# T02_noclock_rev3.net
KiCad netlist of a schematic drawn in EAGLE
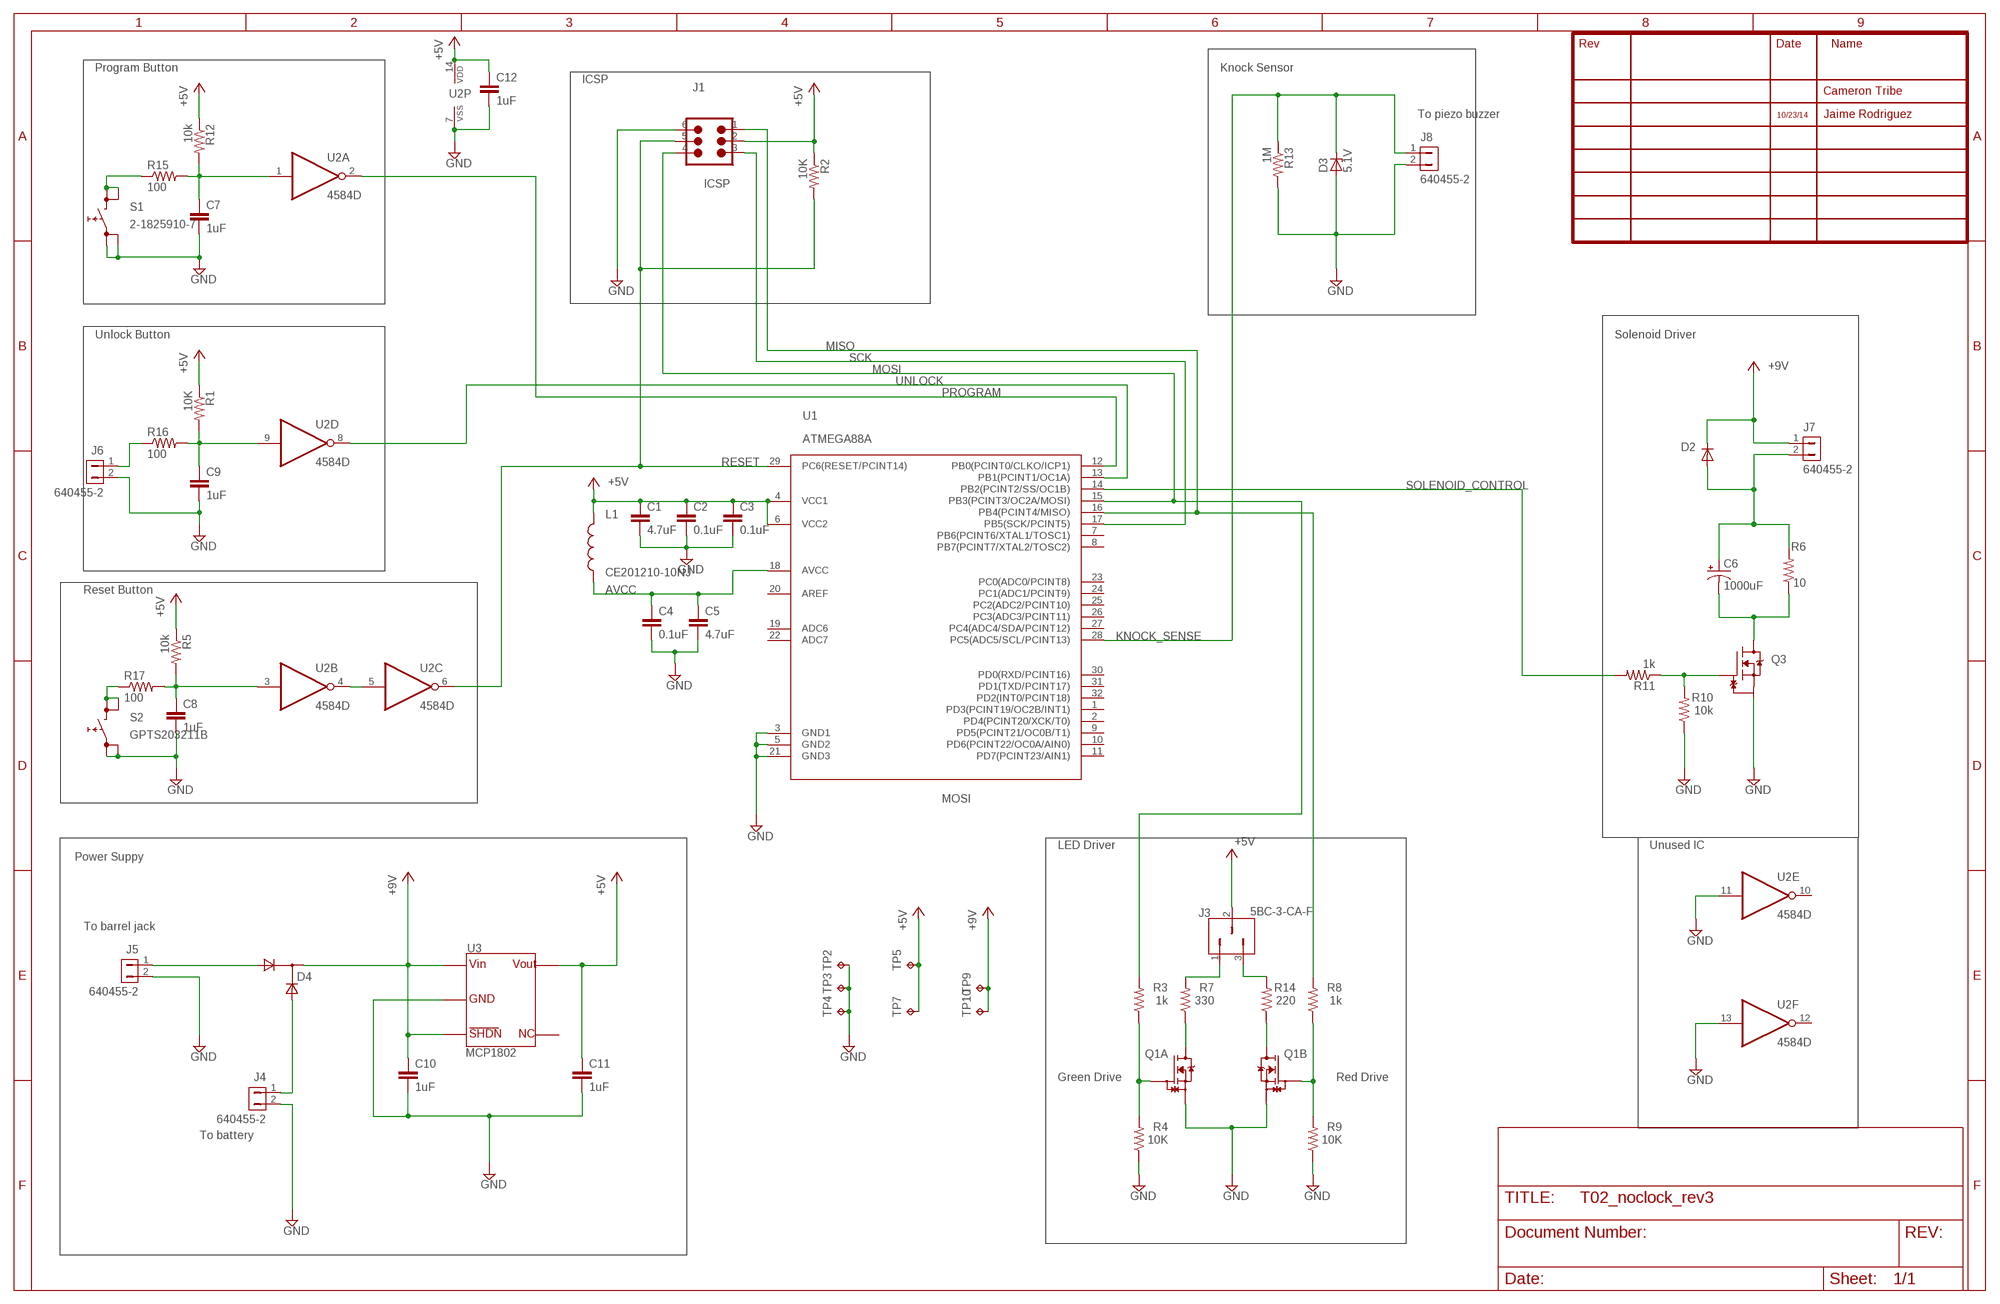
[diagram p0: schematic, sheet 1]

(export (version "E")
  (design (tool "Eeschema 10.0.6"))
  (components
    (comp (ref "C1")
      (value "4.7uF")
      (footprint "eagle-import:C0805")
      (fields (field (name "PARTNUM") "CL21A475KOFNNNE"))
      (libsource (lib "eagle-import") (part "C-EUC0805"))
    )
    (comp (ref "C2")
      (value "0.1uF")
      (footprint "eagle-import:C0805")
      (fields (field (name "PARTNUM") "GRM155R61A104KA01D"))
      (libsource (lib "eagle-import") (part "C-EUC0805"))
    )
    (comp (ref "C3")
      (value "0.1uF")
      (footprint "eagle-import:C0805")
      (fields (field (name "PARTNUM") "GRM155R61A104KA01D"))
      (libsource (lib "eagle-import") (part "C-EUC0805"))
    )
    (comp (ref "C4")
      (value "0.1uF")
      (footprint "eagle-import:C0805")
      (fields (field (name "PARTNUM") "GRM155R61A104KA01D"))
      (libsource (lib "eagle-import") (part "C-EUC0805"))
    )
    (comp (ref "C5")
      (value "4.7uF")
      (footprint "eagle-import:C0805")
      (fields (field (name "PARTNUM") "CL21A475KOFNNNE"))
      (libsource (lib "eagle-import") (part "C-EUC0805"))
    )
    (comp (ref "C6")
      (value "1000uF")
      (footprint "eagle-import:EKY-100ELL102MH20D")
      (libsource (lib "eagle-import") (part "EKY-100ELL102MH20D"))
    )
    (comp (ref "C7")
      (value "1uF")
      (footprint "eagle-import:C0805")
      (fields (field (name "PARTNUM") "CL21B105KBFNNNE"))
      (libsource (lib "eagle-import") (part "C-EUC0805"))
    )
    (comp (ref "C8")
      (value "1uF")
      (footprint "eagle-import:C0805")
      (fields (field (name "PARTNUM") "CL21B105KBFNNNE"))
      (libsource (lib "eagle-import") (part "C-EUC0805"))
    )
    (comp (ref "C9")
      (value "1uF")
      (footprint "eagle-import:C0805")
      (fields (field (name "PARTNUM") "CL21B105KBFNNNE"))
      (libsource (lib "eagle-import") (part "C-EUC0805"))
    )
    (comp (ref "C10")
      (value "1uF")
      (footprint "eagle-import:C0805")
      (fields (field (name "PARTNUM") "CL21B105KBFNNNE"))
      (libsource (lib "eagle-import") (part "C-EUC0805"))
    )
    (comp (ref "C11")
      (value "1uF")
      (footprint "eagle-import:C0805")
      (fields (field (name "PARTNUM") "CL21B105KBFNNNE"))
      (libsource (lib "eagle-import") (part "C-EUC0805"))
    )
    (comp (ref "C12")
      (value "1uF")
      (footprint "eagle-import:C0805")
      (fields (field (name "PARTNUM") "CL21B105KBFNNNE"))
      (libsource (lib "eagle-import") (part "C-EUC0805"))
    )
    (comp (ref "D2")
      (value "GF1")
      (footprint "eagle-import:SMA-DO214AC")
      (fields (field (name "PARTNUM") "S1J"))
      (libsource (lib "eagle-import") (part "GF1"))
    )
    (comp (ref "D3")
      (value "5.1V")
      (footprint "eagle-import:SOT23")
      (fields (field (name "PARTNUM") "BZX84C4V7-TP "))
      (libsource (lib "eagle-import") (part "ZENER-DIODESOT23"))
    )
    (comp (ref "D4")
      (value "PMEG2005CT,215")
      (footprint "eagle-import:SOT-23")
      (libsource (lib "eagle-import") (part "PMEG2005CT,215"))
    )
    (comp (ref "J1")
      (value "ICSP")
      (footprint "eagle-import:ICSP")
      (libsource (lib "eagle-import") (part "ICSP"))
    )
    (comp (ref "J3")
      (value "5BC-3-CA-F")
      (footprint "eagle-import:3_PIN_CONNECTOR")
      (libsource (lib "eagle-import") (part "5BC-3-CA-F"))
    )
    (comp (ref "J4")
      (value "640455-2")
      (footprint "eagle-import:2-PIN_CONNECTOR")
      (libsource (lib "eagle-import") (part "640455-2"))
    )
    (comp (ref "J5")
      (value "640455-2")
      (footprint "eagle-import:2-PIN_CONNECTOR")
      (libsource (lib "eagle-import") (part "640455-2"))
    )
    (comp (ref "J6")
      (value "640455-2")
      (footprint "eagle-import:2-PIN_CONNECTOR")
      (libsource (lib "eagle-import") (part "640455-2"))
    )
    (comp (ref "J7")
      (value "640455-2")
      (footprint "eagle-import:2-PIN_CONNECTOR")
      (libsource (lib "eagle-import") (part "640455-2"))
    )
    (comp (ref "J8")
      (value "640455-2")
      (footprint "eagle-import:2-PIN_CONNECTOR")
      (libsource (lib "eagle-import") (part "640455-2"))
    )
    (comp (ref "L1")
      (value "CE201210-10NJ")
      (footprint "eagle-import:R0805")
      (libsource (lib "eagle-import") (part "CE201210-10NJ"))
    )
    (comp (ref "Q1")
      (value "DMN63D8LDW-7")
      (footprint "eagle-import:SOT363")
      (fields (field (name "PARTNUM") "DMN63D8LDW-7"))
      (libsource (lib "eagle-import") (part "DMN63D8LDW-7"))
    )
    (comp (ref "Q3")
      (value "DMG1012UW-7")
      (footprint "eagle-import:SOT323")
      (libsource (lib "eagle-import") (part "DMG1012UW-7"))
    )
    (comp (ref "R1")
      (value "10K")
      (footprint "eagle-import:R0805")
      (fields (field (name "PARTNUM") "ESR10EZPJ103"))
      (libsource (lib "eagle-import") (part "R-US_R0805"))
    )
    (comp (ref "R2")
      (value "10K")
      (footprint "eagle-import:R0805")
      (fields (field (name "PARTNUM") "ESR10EZPJ103"))
      (libsource (lib "eagle-import") (part "R-US_R0805"))
    )
    (comp (ref "R3")
      (value "1k")
      (footprint "eagle-import:R0805")
      (fields (field (name "PARTNUM") "MCR10ERTF1001"))
      (libsource (lib "eagle-import") (part "R-US_R0805"))
    )
    (comp (ref "R4")
      (value "10K")
      (footprint "eagle-import:R0805")
      (fields (field (name "PARTNUM") "ESR10EZPJ103"))
      (libsource (lib "eagle-import") (part "R-US_R0805"))
    )
    (comp (ref "R5")
      (value "10k")
      (footprint "eagle-import:R0805")
      (fields (field (name "PARTNUM") "ESR10EZPJ103"))
      (libsource (lib "eagle-import") (part "R-US_R0805"))
    )
    (comp (ref "R6")
      (value "10")
      (footprint "eagle-import:R2512")
      (fields (field (name "PARTNUM") "CRM2512-JW-100ELF "))
      (libsource (lib "eagle-import") (part "R-US_R2512"))
    )
    (comp (ref "R7")
      (value "330")
      (footprint "eagle-import:R0805")
      (fields (field (name "PARTNUM") "MCR10ERTF3300"))
      (libsource (lib "eagle-import") (part "R-US_R0805"))
    )
    (comp (ref "R8")
      (value "1k")
      (footprint "eagle-import:R0805")
      (fields (field (name "PARTNUM") "MCR10ERTF1001"))
      (libsource (lib "eagle-import") (part "R-US_R0805"))
    )
    (comp (ref "R9")
      (value "10K")
      (footprint "eagle-import:R0805")
      (fields (field (name "PARTNUM") "ESR10EZPJ103"))
      (libsource (lib "eagle-import") (part "R-US_R0805"))
    )
    (comp (ref "R10")
      (value "10k")
      (footprint "eagle-import:R0805")
      (fields (field (name "PARTNUM") "ESR10EZPJ103"))
      (libsource (lib "eagle-import") (part "R-US_R0805"))
    )
    (comp (ref "R11")
      (value "1k")
      (footprint "eagle-import:R0805")
      (fields (field (name "PARTNUM") "MCR10ERTF1001"))
      (libsource (lib "eagle-import") (part "R-US_R0805"))
    )
    (comp (ref "R12")
      (value "10k")
      (footprint "eagle-import:R0805")
      (fields (field (name "PARTNUM") "ESR10EZPJ103"))
      (libsource (lib "eagle-import") (part "R-US_R0805"))
    )
    (comp (ref "R13")
      (value "1M")
      (footprint "eagle-import:R0805")
      (fields (field (name "PARTNUM") "RMCF0805JT1M00"))
      (libsource (lib "eagle-import") (part "R-US_R0805"))
    )
    (comp (ref "R14")
      (value "220")
      (footprint "eagle-import:R0805")
      (fields (field (name "PARTNUM") "RMCF0805FT220R"))
      (libsource (lib "eagle-import") (part "R-US_R0805"))
    )
    (comp (ref "R15")
      (value "100")
      (footprint "eagle-import:R0805")
      (fields (field (name "PARTNUM") "ESR10EZPJ103"))
      (libsource (lib "eagle-import") (part "R-US_R0805"))
    )
    (comp (ref "R16")
      (value "100")
      (footprint "eagle-import:R0805")
      (fields (field (name "PARTNUM") "ESR10EZPJ103"))
      (libsource (lib "eagle-import") (part "R-US_R0805"))
    )
    (comp (ref "R17")
      (value "100")
      (footprint "eagle-import:R0805")
      (fields (field (name "PARTNUM") "ESR10EZPJ103"))
      (libsource (lib "eagle-import") (part "R-US_R0805"))
    )
    (comp (ref "S1")
      (value "2-1825910-7")
      (footprint "eagle-import:FSM14JH")
      (libsource (lib "eagle-import") (part "2-1825910-7"))
    )
    (comp (ref "S2")
      (value "GPTS203211B")
      (footprint "eagle-import:GPTS203211B")
      (libsource (lib "eagle-import") (part "GPTS203211B"))
    )
    (comp (ref "TP2")
      (value "TPTP19R")
      (footprint "eagle-import:TP19R")
      (libsource (lib "eagle-import") (part "TPTP19R"))
    )
    (comp (ref "TP3")
      (value "TPTP19R")
      (footprint "eagle-import:TP19R")
      (libsource (lib "eagle-import") (part "TPTP19R"))
    )
    (comp (ref "TP4")
      (value "TPTP19R")
      (footprint "eagle-import:TP19R")
      (libsource (lib "eagle-import") (part "TPTP19R"))
    )
    (comp (ref "TP5")
      (value "TPTP19R")
      (footprint "eagle-import:TP19R")
      (libsource (lib "eagle-import") (part "TPTP19R"))
    )
    (comp (ref "TP7")
      (value "TPTP19R")
      (footprint "eagle-import:TP19R")
      (libsource (lib "eagle-import") (part "TPTP19R"))
    )
    (comp (ref "TP9")
      (value "TPTP19R")
      (footprint "eagle-import:TP19R")
      (libsource (lib "eagle-import") (part "TPTP19R"))
    )
    (comp (ref "TP10")
      (value "TPTP19R")
      (footprint "eagle-import:TP19R")
      (libsource (lib "eagle-import") (part "TPTP19R"))
    )
    (comp (ref "U1")
      (value "ATMEGA88A")
      (footprint "eagle-import:TQFP32")
      (libsource (lib "eagle-import") (part "ATMEGA88A"))
    )
    (comp (ref "U2")
      (value "4584D")
      (footprint "eagle-import:SO14")
      (fields (field (name "PARTNUM") "4584D"))
      (libsource (lib "eagle-import") (part "4584D"))
    )
    (comp (ref "U3")
      (value "MCP1802")
      (footprint "eagle-import:SOT23-5")
      (libsource (lib "eagle-import") (part "MCP1802"))
    )
  )
  (nets
    (net (code "1") (name "+5V") (class "Default")
      (node (ref "C1") (pin "1") (pinfunction "1_1") (pintype "passive"))
      (node (ref "C11") (pin "1") (pinfunction "1_1") (pintype "passive"))
      (node (ref "C12") (pin "1") (pinfunction "1_1") (pintype "passive"))
      (node (ref "C2") (pin "1") (pinfunction "1_1") (pintype "passive"))
      (node (ref "C3") (pin "1") (pinfunction "1_1") (pintype "passive"))
      (node (ref "J1") (pin "2") (pinfunction "2_2") (pintype "passive"))
      (node (ref "J3") (pin "2") (pinfunction "2_2") (pintype "passive"))
      (node (ref "L1") (pin "2") (pinfunction "2_2") (pintype "passive"))
      (node (ref "R1") (pin "1") (pinfunction "1_1") (pintype "passive"))
      (node (ref "R12") (pin "1") (pinfunction "1_1") (pintype "passive"))
      (node (ref "R2") (pin "1") (pinfunction "1_1") (pintype "passive"))
      (node (ref "R5") (pin "1") (pinfunction "1_1") (pintype "passive"))
      (node (ref "TP5") (pin "TP") (pinfunction "TP_TP") (pintype "input"))
      (node (ref "TP7") (pin "TP") (pinfunction "TP_TP") (pintype "input"))
      (node (ref "U1") (pin "4") (pinfunction "VCC1_4") (pintype "power_in"))
      (node (ref "U1") (pin "6") (pinfunction "VCC2_6") (pintype "passive"))
      (node (ref "U2") (pin "14") (pinfunction "VDD_14") (pintype "power_in"))
      (node (ref "U3") (pin "5") (pinfunction "VOUT_5") (pintype "passive"))
    )
    (net (code "2") (name "+9V") (class "Default")
      (node (ref "C10") (pin "1") (pinfunction "1_1") (pintype "passive"))
      (node (ref "D2") (pin "K") (pinfunction "C_K") (pintype "passive"))
      (node (ref "D4") (pin "2") (pinfunction "C_2") (pintype "passive"))
      (node (ref "J7") (pin "1") (pinfunction "1_1") (pintype "passive"))
      (node (ref "TP10") (pin "TP") (pinfunction "TP_TP") (pintype "input"))
      (node (ref "TP9") (pin "TP") (pinfunction "TP_TP") (pintype "input"))
      (node (ref "U3") (pin "1") (pinfunction "VIN_1") (pintype "passive"))
      (node (ref "U3") (pin "3") (pinfunction "SHDN_3") (pintype "passive"))
    )
    (net (code "3") (name "/AVCC") (class "Default")
      (node (ref "C4") (pin "1") (pinfunction "1_1") (pintype "passive"))
      (node (ref "C5") (pin "1") (pinfunction "1_1") (pintype "passive"))
      (node (ref "L1") (pin "1") (pinfunction "1_1") (pintype "passive"))
      (node (ref "U1") (pin "18") (pinfunction "AVCC_18") (pintype "power_in"))
    )
    (net (code "4") (name "/KNOCK_SENSE") (class "Default")
      (node (ref "D3") (pin "3") (pinfunction "C_3") (pintype "passive"))
      (node (ref "J8") (pin "1") (pinfunction "1_1") (pintype "passive"))
      (node (ref "R13") (pin "1") (pinfunction "1_1") (pintype "passive"))
      (node (ref "U1") (pin "28") (pinfunction "PC5(ADC5/SCL/PCINT13)_28") (pintype "bidirectional"))
    )
    (net (code "5") (name "/MISO") (class "Default")
      (node (ref "J1") (pin "1") (pinfunction "1_1") (pintype "passive"))
      (node (ref "R8") (pin "2") (pinfunction "2_2") (pintype "passive"))
      (node (ref "U1") (pin "16") (pinfunction "PB4(PCINT4/MISO)_16") (pintype "bidirectional"))
    )
    (net (code "6") (name "/MOSI") (class "Default")
      (node (ref "J1") (pin "4") (pinfunction "4_4") (pintype "passive"))
      (node (ref "R3") (pin "2") (pinfunction "2_2") (pintype "passive"))
      (node (ref "U1") (pin "15") (pinfunction "PB3(PCINT3/OC2A/MOSI)_15") (pintype "bidirectional"))
    )
    (net (code "7") (name "/PROGRAM") (class "Default")
      (node (ref "U1") (pin "12") (pinfunction "PB0(PCINT0/CLKO/ICP1)_12") (pintype "bidirectional"))
      (node (ref "U2") (pin "2") (pinfunction "O_2") (pintype "output"))
    )
    (net (code "8") (name "/RESET") (class "Default")
      (node (ref "J1") (pin "5") (pinfunction "5_5") (pintype "passive"))
      (node (ref "R2") (pin "2") (pinfunction "2_2") (pintype "passive"))
      (node (ref "U1") (pin "29") (pinfunction "PC6(RESET/PCINT14)_29") (pintype "bidirectional"))
      (node (ref "U2") (pin "6") (pinfunction "O_6") (pintype "output"))
    )
    (net (code "9") (name "/SCK") (class "Default")
      (node (ref "J1") (pin "3") (pinfunction "3_3") (pintype "passive"))
      (node (ref "U1") (pin "17") (pinfunction "PB5(SCK/PCINT5)_17") (pintype "bidirectional"))
    )
    (net (code "10") (name "/SOLENOID_CONTROL") (class "Default")
      (node (ref "R11") (pin "2") (pinfunction "2_2") (pintype "passive"))
      (node (ref "U1") (pin "14") (pinfunction "PB2(PCINT2/SS/OC1B)_14") (pintype "bidirectional"))
    )
    (net (code "11") (name "/UNLOCK") (class "Default")
      (node (ref "U1") (pin "13") (pinfunction "PB1(PCINT1/OC1A)_13") (pintype "bidirectional"))
      (node (ref "U2") (pin "8") (pinfunction "O_8") (pintype "output"))
    )
    (net (code "12") (name "GND") (class "Default")
      (node (ref "C1") (pin "2") (pinfunction "2_2") (pintype "passive"))
      (node (ref "C10") (pin "2") (pinfunction "2_2") (pintype "passive"))
      (node (ref "C11") (pin "2") (pinfunction "2_2") (pintype "passive"))
      (node (ref "C12") (pin "2") (pinfunction "2_2") (pintype "passive"))
      (node (ref "C2") (pin "2") (pinfunction "2_2") (pintype "passive"))
      (node (ref "C3") (pin "2") (pinfunction "2_2") (pintype "passive"))
      (node (ref "C4") (pin "2") (pinfunction "2_2") (pintype "passive"))
      (node (ref "C5") (pin "2") (pinfunction "2_2") (pintype "passive"))
      (node (ref "C7") (pin "2") (pinfunction "2_2") (pintype "passive"))
      (node (ref "C8") (pin "2") (pinfunction "2_2") (pintype "passive"))
      (node (ref "C9") (pin "2") (pinfunction "2_2") (pintype "passive"))
      (node (ref "D3") (pin "1") (pinfunction "A_1") (pintype "passive"))
      (node (ref "J1") (pin "6") (pinfunction "6_6") (pintype "passive"))
      (node (ref "J4") (pin "2") (pinfunction "2_2") (pintype "passive"))
      (node (ref "J5") (pin "2") (pinfunction "2_2") (pintype "passive"))
      (node (ref "J6") (pin "2") (pinfunction "2_2") (pintype "passive"))
      (node (ref "J8") (pin "2") (pinfunction "2_2") (pintype "passive"))
      (node (ref "Q1") (pin "S1") (pinfunction "S_S1") (pintype "passive"))
      (node (ref "Q1") (pin "S2") (pinfunction "S_S2") (pintype "passive"))
      (node (ref "Q3") (pin "3") (pinfunction "S_3") (pintype "passive"))
      (node (ref "R10") (pin "1") (pinfunction "1_1") (pintype "passive"))
      (node (ref "R13") (pin "2") (pinfunction "2_2") (pintype "passive"))
      (node (ref "R4") (pin "1") (pinfunction "1_1") (pintype "passive"))
      (node (ref "R9") (pin "1") (pinfunction "1_1") (pintype "passive"))
      (node (ref "S1") (pin "1") (pinfunction "1_1") (pintype "passive"))
      (node (ref "S1") (pin "2") (pinfunction "2_2") (pintype "passive"))
      (node (ref "S2") (pin "1") (pinfunction "1_1") (pintype "passive"))
      (node (ref "S2") (pin "2") (pinfunction "2_2") (pintype "passive"))
      (node (ref "TP2") (pin "TP") (pinfunction "TP_TP") (pintype "input"))
      (node (ref "TP3") (pin "TP") (pinfunction "TP_TP") (pintype "input"))
      (node (ref "TP4") (pin "TP") (pinfunction "TP_TP") (pintype "input"))
      (node (ref "U1") (pin "21") (pinfunction "GND3_21") (pintype "power_in"))
      (node (ref "U1") (pin "3") (pinfunction "GND1_3") (pintype "power_in"))
      (node (ref "U1") (pin "5") (pinfunction "GND2_5") (pintype "power_in"))
      (node (ref "U2") (pin "11") (pinfunction "I_11") (pintype "input"))
      (node (ref "U2") (pin "13") (pinfunction "I_13") (pintype "input"))
      (node (ref "U2") (pin "7") (pinfunction "VSS_7") (pintype "power_in"))
      (node (ref "U3") (pin "2") (pinfunction "GND_2") (pintype "power_in"))
    )
    (net (code "13") (name "Net-(C6-Pad+)") (class "Default")
      (node (ref "C6") (pin "+") (pinfunction "+_+") (pintype "passive"))
      (node (ref "D2") (pin "A") (pinfunction "A_A") (pintype "passive"))
      (node (ref "J7") (pin "2") (pinfunction "2_2") (pintype "passive"))
      (node (ref "R6") (pin "2") (pinfunction "2_2") (pintype "passive"))
    )
    (net (code "14") (name "Net-(D4-A1)") (class "Default")
      (node (ref "D4") (pin "3") (pinfunction "A1_3") (pintype "passive"))
      (node (ref "J5") (pin "1") (pinfunction "1_1") (pintype "passive"))
    )
    (net (code "15") (name "Net-(D4-A2)") (class "Default")
      (node (ref "D4") (pin "1") (pinfunction "A2_1") (pintype "passive"))
      (node (ref "J4") (pin "1") (pinfunction "1_1") (pintype "passive"))
    )
    (net (code "16") (name "Net-(J3-Pad1)") (class "Default")
      (node (ref "J3") (pin "1") (pinfunction "1_1") (pintype "passive"))
      (node (ref "R7") (pin "2") (pinfunction "2_2") (pintype "passive"))
    )
    (net (code "17") (name "Net-(J3-Pad3)") (class "Default")
      (node (ref "J3") (pin "3") (pinfunction "3_3") (pintype "passive"))
      (node (ref "R14") (pin "2") (pinfunction "2_2") (pintype "passive"))
    )
    (net (code "18") (name "Net-(J6-Pad1)") (class "Default")
      (node (ref "J6") (pin "1") (pinfunction "1_1") (pintype "passive"))
      (node (ref "R16") (pin "1") (pinfunction "1_1") (pintype "passive"))
    )
    (net (code "19") (name "Net-(Q1A-D)") (class "Default")
      (node (ref "Q1") (pin "D1") (pinfunction "D_D1") (pintype "passive"))
      (node (ref "R7") (pin "1") (pinfunction "1_1") (pintype "passive"))
    )
    (net (code "20") (name "Net-(Q1A-G)") (class "Default")
      (node (ref "Q1") (pin "G1") (pinfunction "G_G1") (pintype "passive"))
      (node (ref "R3") (pin "1") (pinfunction "1_1") (pintype "passive"))
      (node (ref "R4") (pin "2") (pinfunction "2_2") (pintype "passive"))
    )
    (net (code "21") (name "Net-(Q1B-D)") (class "Default")
      (node (ref "Q1") (pin "D2") (pinfunction "D_D2") (pintype "passive"))
      (node (ref "R14") (pin "1") (pinfunction "1_1") (pintype "passive"))
    )
    (net (code "22") (name "Net-(Q1B-G)") (class "Default")
      (node (ref "Q1") (pin "G2") (pinfunction "G_G2") (pintype "passive"))
      (node (ref "R8") (pin "1") (pinfunction "1_1") (pintype "passive"))
      (node (ref "R9") (pin "2") (pinfunction "2_2") (pintype "passive"))
    )
    (net (code "23") (name "Net-(Q3-D)") (class "Default")
      (node (ref "C6") (pin "-") (pinfunction "-_-") (pintype "passive"))
      (node (ref "Q3") (pin "1") (pinfunction "D_1") (pintype "passive"))
      (node (ref "R6") (pin "1") (pinfunction "1_1") (pintype "passive"))
    )
    (net (code "24") (name "Net-(Q3-G)") (class "Default")
      (node (ref "Q3") (pin "2") (pinfunction "G_2") (pintype "passive"))
      (node (ref "R10") (pin "2") (pinfunction "2_2") (pintype "passive"))
      (node (ref "R11") (pin "1") (pinfunction "1_1") (pintype "passive"))
    )
    (net (code "25") (name "Net-(R15-Pad1)") (class "Default")
      (node (ref "R15") (pin "1") (pinfunction "1_1") (pintype "passive"))
      (node (ref "S1") (pin "3") (pinfunction "3_3") (pintype "passive"))
      (node (ref "S1") (pin "4") (pinfunction "4_4") (pintype "passive"))
    )
    (net (code "26") (name "Net-(R17-Pad1)") (class "Default")
      (node (ref "R17") (pin "1") (pinfunction "1_1") (pintype "passive"))
      (node (ref "S2") (pin "3") (pinfunction "3_3") (pintype "passive"))
      (node (ref "S2") (pin "4") (pinfunction "4_4") (pintype "passive"))
    )
    (net (code "27") (name "Net-(U2A-I)") (class "Default")
      (node (ref "C7") (pin "1") (pinfunction "1_1") (pintype "passive"))
      (node (ref "R12") (pin "2") (pinfunction "2_2") (pintype "passive"))
      (node (ref "R15") (pin "2") (pinfunction "2_2") (pintype "passive"))
      (node (ref "U2") (pin "1") (pinfunction "I_1") (pintype "input"))
    )
    (net (code "28") (name "Net-(U2B-I)") (class "Default")
      (node (ref "C8") (pin "1") (pinfunction "1_1") (pintype "passive"))
      (node (ref "R17") (pin "2") (pinfunction "2_2") (pintype "passive"))
      (node (ref "R5") (pin "2") (pinfunction "2_2") (pintype "passive"))
      (node (ref "U2") (pin "3") (pinfunction "I_3") (pintype "input"))
    )
    (net (code "29") (name "Net-(U2B-O)") (class "Default")
      (node (ref "U2") (pin "4") (pinfunction "O_4") (pintype "output"))
      (node (ref "U2") (pin "5") (pinfunction "I_5") (pintype "input"))
    )
    (net (code "30") (name "Net-(U2D-I)") (class "Default")
      (node (ref "C9") (pin "1") (pinfunction "1_1") (pintype "passive"))
      (node (ref "R1") (pin "2") (pinfunction "2_2") (pintype "passive"))
      (node (ref "R16") (pin "2") (pinfunction "2_2") (pintype "passive"))
      (node (ref "U2") (pin "9") (pinfunction "I_9") (pintype "input"))
    )
    (net (code "31") (name "unconnected-(U1-ADC6-Pad19)") (class "Default")
      (node (ref "U1") (pin "19") (pinfunction "ADC6_19") (pintype "bidirectional"))
    )
    (net (code "32") (name "unconnected-(U1-ADC7-Pad22)") (class "Default")
      (node (ref "U1") (pin "22") (pinfunction "ADC7_22") (pintype "bidirectional"))
    )
    (net (code "33") (name "unconnected-(U1-AREF-Pad20)") (class "Default")
      (node (ref "U1") (pin "20") (pinfunction "AREF_20") (pintype "passive"))
    )
    (net (code "34") (name "unconnected-(U1-PB6(PCINT6{slash}XTAL1{slash}TOSC1)-Pad7)") (class "Default")
      (node (ref "U1") (pin "7") (pinfunction "PB6(PCINT6/XTAL1/TOSC1)_7") (pintype "bidirectional"))
    )
    (net (code "35") (name "unconnected-(U1-PB7(PCINT7{slash}XTAL2{slash}TOSC2)-Pad8)") (class "Default")
      (node (ref "U1") (pin "8") (pinfunction "PB7(PCINT7/XTAL2/TOSC2)_8") (pintype "bidirectional"))
    )
    (net (code "36") (name "unconnected-(U1-PC0(ADC0{slash}PCINT8)-Pad23)") (class "Default")
      (node (ref "U1") (pin "23") (pinfunction "PC0(ADC0/PCINT8)_23") (pintype "bidirectional"))
    )
    (net (code "37") (name "unconnected-(U1-PC1(ADC1{slash}PCINT9)-Pad24)") (class "Default")
      (node (ref "U1") (pin "24") (pinfunction "PC1(ADC1/PCINT9)_24") (pintype "bidirectional"))
    )
    (net (code "38") (name "unconnected-(U1-PC2(ADC2{slash}PCINT10)-Pad25)") (class "Default")
      (node (ref "U1") (pin "25") (pinfunction "PC2(ADC2/PCINT10)_25") (pintype "bidirectional"))
    )
    (net (code "39") (name "unconnected-(U1-PC3(ADC3{slash}PCINT11)-Pad26)") (class "Default")
      (node (ref "U1") (pin "26") (pinfunction "PC3(ADC3/PCINT11)_26") (pintype "bidirectional"))
    )
    (net (code "40") (name "unconnected-(U1-PC4(ADC4{slash}SDA{slash}PCINT12)-Pad27)") (class "Default")
      (node (ref "U1") (pin "27") (pinfunction "PC4(ADC4/SDA/PCINT12)_27") (pintype "bidirectional"))
    )
    (net (code "41") (name "unconnected-(U1-PD0(RXD{slash}PCINT16)-Pad30)") (class "Default")
      (node (ref "U1") (pin "30") (pinfunction "PD0(RXD/PCINT16)_30") (pintype "bidirectional"))
    )
    (net (code "42") (name "unconnected-(U1-PD1(TXD{slash}PCINT17)-Pad31)") (class "Default")
      (node (ref "U1") (pin "31") (pinfunction "PD1(TXD/PCINT17)_31") (pintype "bidirectional"))
    )
    (net (code "43") (name "unconnected-(U1-PD2(INT0{slash}PCINT18)-Pad32)") (class "Default")
      (node (ref "U1") (pin "32") (pinfunction "PD2(INT0/PCINT18)_32") (pintype "bidirectional"))
    )
    (net (code "44") (name "unconnected-(U1-PD3(PCINT19{slash}OC2B{slash}INT1)-Pad1)") (class "Default")
      (node (ref "U1") (pin "1") (pinfunction "PD3(PCINT19/OC2B/INT1)_1") (pintype "bidirectional"))
    )
    (net (code "45") (name "unconnected-(U1-PD4(PCINT20{slash}XCK{slash}T0)-Pad2)") (class "Default")
      (node (ref "U1") (pin "2") (pinfunction "PD4(PCINT20/XCK/T0)_2") (pintype "bidirectional"))
    )
    (net (code "46") (name "unconnected-(U1-PD5(PCINT21{slash}OC0B{slash}T1)-Pad9)") (class "Default")
      (node (ref "U1") (pin "9") (pinfunction "PD5(PCINT21/OC0B/T1)_9") (pintype "bidirectional"))
    )
    (net (code "47") (name "unconnected-(U1-PD6(PCINT22{slash}OC0A{slash}AIN0)-Pad10)") (class "Default")
      (node (ref "U1") (pin "10") (pinfunction "PD6(PCINT22/OC0A/AIN0)_10") (pintype "bidirectional"))
    )
    (net (code "48") (name "unconnected-(U1-PD7(PCINT23{slash}AIN1)-Pad11)") (class "Default")
      (node (ref "U1") (pin "11") (pinfunction "PD7(PCINT23/AIN1)_11") (pintype "bidirectional"))
    )
    (net (code "49") (name "unconnected-(U2E-O-Pad10)") (class "Default")
      (node (ref "U2") (pin "10") (pinfunction "O_10") (pintype "output"))
    )
    (net (code "50") (name "unconnected-(U2F-O-Pad12)") (class "Default")
      (node (ref "U2") (pin "12") (pinfunction "O_12") (pintype "output"))
    )
    (net (code "51") (name "unconnected-(U3-NC-Pad4)") (class "Default")
      (node (ref "U3") (pin "4") (pinfunction "NC_4") (pintype "no_connect"))
    )
  )
)
